# board_with_arduinomicr3.net
KiCad netlist of a schematic drawn in EAGLE
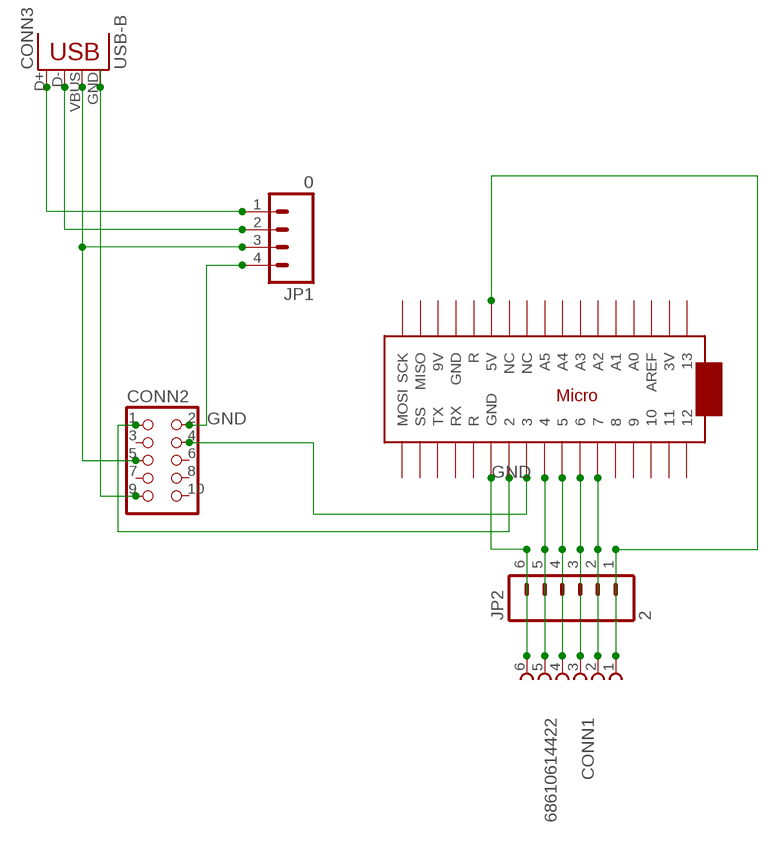
[diagram p0: schematic, sheet 1]

(export (version "E")
  (design (tool "Eeschema 10.0.6"))
  (components
    (comp (ref "CONN1")
      (value "68610614422")
      (footprint "eagle-import:68610614422")
      (libsource (lib "eagle-import") (part "68610614422"))
    )
    (comp (ref "CONN2")
      (value "CON_HEADER_2X05-PTH+SHROUDED_A")
      (footprint "eagle-import:PINSHRD_PTH_2X05")
      (libsource (lib "eagle-import") (part "CON_HEADER_2X05-PTH+SHROUDED_A"))
    )
    (comp (ref "CONN3")
      (value "USB-B")
      (footprint "eagle-import:USB-B-PTH")
      (libsource (lib "eagle-import") (part "USBPTH"))
    )
    (comp (ref "JP1")
      (value "0")
      (footprint "eagle-import:1X04_LONGPADS")
      (libsource (lib "eagle-import") (part "M04LONGPADS"))
    )
    (comp (ref "JP2")
      (value "2")
      (footprint "eagle-import:1X06_LOCK_LONGPADS")
      (libsource (lib "eagle-import") (part "M06LOCK_LONGPADS"))
    )
    (comp (ref "U$1")
      (value "ARDUINOMICRO")
      (footprint "eagle-import:ARDUINOMICRO")
      (libsource (lib "eagle-import") (part "ARDUINOMICRO"))
    )
  )
  (nets
    (net (code "1") (name "/GND") (class "Default")
      (node (ref "CONN1") (pin "6") (pinfunction "6_6") (pintype "passive"))
      (node (ref "CONN2") (pin "2") (pinfunction "2_2") (pintype "passive"))
      (node (ref "JP1") (pin "4") (pinfunction "4_4") (pintype "passive"))
      (node (ref "JP2") (pin "6") (pinfunction "6_6") (pintype "passive"))
      (node (ref "U$1") (pin "P$21") (pinfunction "GND_P$21") (pintype "bidirectional"))
    )
    (net (code "2") (name "Net-(CONN2-Pad5)") (class "Default")
      (node (ref "CONN2") (pin "5") (pinfunction "5_5") (pintype "passive"))
      (node (ref "CONN3") (pin "VBUS") (pinfunction "VBUS_VBUS") (pintype "bidirectional"))
      (node (ref "JP1") (pin "3") (pinfunction "3_3") (pintype "passive"))
    )
    (net (code "3") (name "Net-(CONN2-Pad9)") (class "Default")
      (node (ref "CONN2") (pin "9") (pinfunction "9_9") (pintype "passive"))
      (node (ref "CONN3") (pin "GND") (pinfunction "GND_GND") (pintype "bidirectional"))
    )
    (net (code "4") (name "Net-(CONN3-PadD+)") (class "Default")
      (node (ref "CONN3") (pin "D+") (pinfunction "D+_D+") (pintype "bidirectional"))
      (node (ref "JP1") (pin "1") (pinfunction "1_1") (pintype "passive"))
    )
    (net (code "5") (name "Net-(CONN3-PadD-)") (class "Default")
      (node (ref "CONN3") (pin "D-") (pinfunction "D-_D-") (pintype "bidirectional"))
      (node (ref "JP1") (pin "2") (pinfunction "2_2") (pintype "passive"))
    )
    (net (code "6") (name "Net-(U$1-2)") (class "Default")
      (node (ref "CONN2") (pin "1") (pinfunction "1_1") (pintype "passive"))
      (node (ref "U$1") (pin "P$11") (pinfunction "2_P$11") (pintype "bidirectional"))
    )
    (net (code "7") (name "Net-(U$1-3)") (class "Default")
      (node (ref "CONN2") (pin "4") (pinfunction "4_4") (pintype "passive"))
      (node (ref "U$1") (pin "P$10") (pinfunction "3_P$10") (pintype "bidirectional"))
    )
    (net (code "8") (name "Net-(U$1-4)") (class "Default")
      (node (ref "CONN1") (pin "5") (pinfunction "5_5") (pintype "passive"))
      (node (ref "JP2") (pin "5") (pinfunction "5_5") (pintype "passive"))
      (node (ref "U$1") (pin "P$9") (pinfunction "4_P$9") (pintype "bidirectional"))
    )
    (net (code "9") (name "Net-(U$1-5)") (class "Default")
      (node (ref "CONN1") (pin "4") (pinfunction "4_4") (pintype "passive"))
      (node (ref "JP2") (pin "4") (pinfunction "4_4") (pintype "passive"))
      (node (ref "U$1") (pin "P$8") (pinfunction "5_P$8") (pintype "bidirectional"))
    )
    (net (code "10") (name "Net-(U$1-5V)") (class "Default")
      (node (ref "CONN1") (pin "1") (pinfunction "1_1") (pintype "passive"))
      (node (ref "JP2") (pin "1") (pinfunction "1_1") (pintype "passive"))
      (node (ref "U$1") (pin "P$23") (pinfunction "5V_P$23") (pintype "bidirectional"))
    )
    (net (code "11") (name "Net-(U$1-6)") (class "Default")
      (node (ref "CONN1") (pin "3") (pinfunction "3_3") (pintype "passive"))
      (node (ref "JP2") (pin "3") (pinfunction "3_3") (pintype "passive"))
      (node (ref "U$1") (pin "P$7") (pinfunction "6_P$7") (pintype "bidirectional"))
    )
    (net (code "12") (name "Net-(U$1-7)") (class "Default")
      (node (ref "CONN1") (pin "2") (pinfunction "2_2") (pintype "passive"))
      (node (ref "JP2") (pin "2") (pinfunction "2_2") (pintype "passive"))
      (node (ref "U$1") (pin "P$6") (pinfunction "7_P$6") (pintype "bidirectional"))
    )
    (net (code "13") (name "unconnected-(CONN2-Pad3)") (class "Default")
      (node (ref "CONN2") (pin "3") (pinfunction "3_3") (pintype "passive"))
    )
    (net (code "14") (name "unconnected-(CONN2-Pad6)") (class "Default")
      (node (ref "CONN2") (pin "6") (pinfunction "6_6") (pintype "passive"))
    )
    (net (code "15") (name "unconnected-(CONN2-Pad7)") (class "Default")
      (node (ref "CONN2") (pin "7") (pinfunction "7_7") (pintype "passive"))
    )
    (net (code "16") (name "unconnected-(CONN2-Pad8)") (class "Default")
      (node (ref "CONN2") (pin "8") (pinfunction "8_8") (pintype "passive"))
    )
    (net (code "17") (name "unconnected-(CONN2-Pad10)") (class "Default")
      (node (ref "CONN2") (pin "10") (pinfunction "10_10") (pintype "passive"))
    )
    (net (code "18") (name "unconnected-(U$1-3V-PadP$33)") (class "Default")
      (node (ref "U$1") (pin "P$33") (pinfunction "3V_P$33") (pintype "bidirectional"))
    )
    (net (code "19") (name "unconnected-(U$1-8-PadP$5)") (class "Default")
      (node (ref "U$1") (pin "P$5") (pinfunction "8_P$5") (pintype "bidirectional"))
    )
    (net (code "20") (name "unconnected-(U$1-9-PadP$4)") (class "Default")
      (node (ref "U$1") (pin "P$4") (pinfunction "9_P$4") (pintype "bidirectional"))
    )
    (net (code "21") (name "unconnected-(U$1-9V-PadP$20)") (class "Default")
      (node (ref "U$1") (pin "P$20") (pinfunction "9V_P$20") (pintype "bidirectional"))
    )
    (net (code "22") (name "unconnected-(U$1-10-PadP$3)") (class "Default")
      (node (ref "U$1") (pin "P$3") (pinfunction "10_P$3") (pintype "bidirectional"))
    )
    (net (code "23") (name "unconnected-(U$1-11-PadP$2)") (class "Default")
      (node (ref "U$1") (pin "P$2") (pinfunction "11_P$2") (pintype "bidirectional"))
    )
    (net (code "24") (name "unconnected-(U$1-12-PadP$1)") (class "Default")
      (node (ref "U$1") (pin "P$1") (pinfunction "12_P$1") (pintype "bidirectional"))
    )
    (net (code "25") (name "unconnected-(U$1-13-PadP$34)") (class "Default")
      (node (ref "U$1") (pin "P$34") (pinfunction "13_P$34") (pintype "bidirectional"))
    )
    (net (code "26") (name "unconnected-(U$1-A0-PadP$31)") (class "Default")
      (node (ref "U$1") (pin "P$31") (pinfunction "A0_P$31") (pintype "bidirectional"))
    )
    (net (code "27") (name "unconnected-(U$1-A1-PadP$30)") (class "Default")
      (node (ref "U$1") (pin "P$30") (pinfunction "A1_P$30") (pintype "bidirectional"))
    )
    (net (code "28") (name "unconnected-(U$1-A2-PadP$29)") (class "Default")
      (node (ref "U$1") (pin "P$29") (pinfunction "A2_P$29") (pintype "bidirectional"))
    )
    (net (code "29") (name "unconnected-(U$1-A3-PadP$28)") (class "Default")
      (node (ref "U$1") (pin "P$28") (pinfunction "A3_P$28") (pintype "bidirectional"))
    )
    (net (code "30") (name "unconnected-(U$1-A4-PadP$27)") (class "Default")
      (node (ref "U$1") (pin "P$27") (pinfunction "A4_P$27") (pintype "bidirectional"))
    )
    (net (code "31") (name "unconnected-(U$1-A5-PadP$26)") (class "Default")
      (node (ref "U$1") (pin "P$26") (pinfunction "A5_P$26") (pintype "bidirectional"))
    )
    (net (code "32") (name "unconnected-(U$1-AREF-PadP$32)") (class "Default")
      (node (ref "U$1") (pin "P$32") (pinfunction "AREF_P$32") (pintype "bidirectional"))
    )
    (net (code "33") (name "unconnected-(U$1-GND-PadP$12)") (class "Default")
      (node (ref "U$1") (pin "P$12") (pinfunction "GND_P$12") (pintype "bidirectional"))
    )
    (net (code "34") (name "unconnected-(U$1-MISO-PadP$19)") (class "Default")
      (node (ref "U$1") (pin "P$19") (pinfunction "MISO_P$19") (pintype "bidirectional"))
    )
    (net (code "35") (name "unconnected-(U$1-MOSI-PadP$17)") (class "Default")
      (node (ref "U$1") (pin "P$17") (pinfunction "MOSI_P$17") (pintype "bidirectional"))
    )
    (net (code "36") (name "unconnected-(U$1-NC-PadP$24)") (class "Default")
      (node (ref "U$1") (pin "P$24") (pinfunction "NC_P$24") (pintype "bidirectional"))
    )
    (net (code "37") (name "unconnected-(U$1-NC-PadP$25)") (class "Default")
      (node (ref "U$1") (pin "P$25") (pinfunction "NC_P$25") (pintype "bidirectional"))
    )
    (net (code "38") (name "unconnected-(U$1-R-PadP$13)") (class "Default")
      (node (ref "U$1") (pin "P$13") (pinfunction "R_P$13") (pintype "bidirectional"))
    )
    (net (code "39") (name "unconnected-(U$1-R-PadP$22)") (class "Default")
      (node (ref "U$1") (pin "P$22") (pinfunction "R_P$22") (pintype "bidirectional"))
    )
    (net (code "40") (name "unconnected-(U$1-RX-PadP$14)") (class "Default")
      (node (ref "U$1") (pin "P$14") (pinfunction "RX_P$14") (pintype "bidirectional"))
    )
    (net (code "41") (name "unconnected-(U$1-SCK-PadP$18)") (class "Default")
      (node (ref "U$1") (pin "P$18") (pinfunction "SCK_P$18") (pintype "bidirectional"))
    )
    (net (code "42") (name "unconnected-(U$1-SS-PadP$16)") (class "Default")
      (node (ref "U$1") (pin "P$16") (pinfunction "SS_P$16") (pintype "bidirectional"))
    )
    (net (code "43") (name "unconnected-(U$1-TX-PadP$15)") (class "Default")
      (node (ref "U$1") (pin "P$15") (pinfunction "TX_P$15") (pintype "bidirectional"))
    )
  )
)
